# BLUEPILL_full_schematic_for_BRD.net
KiCad netlist of a schematic drawn in EAGLE
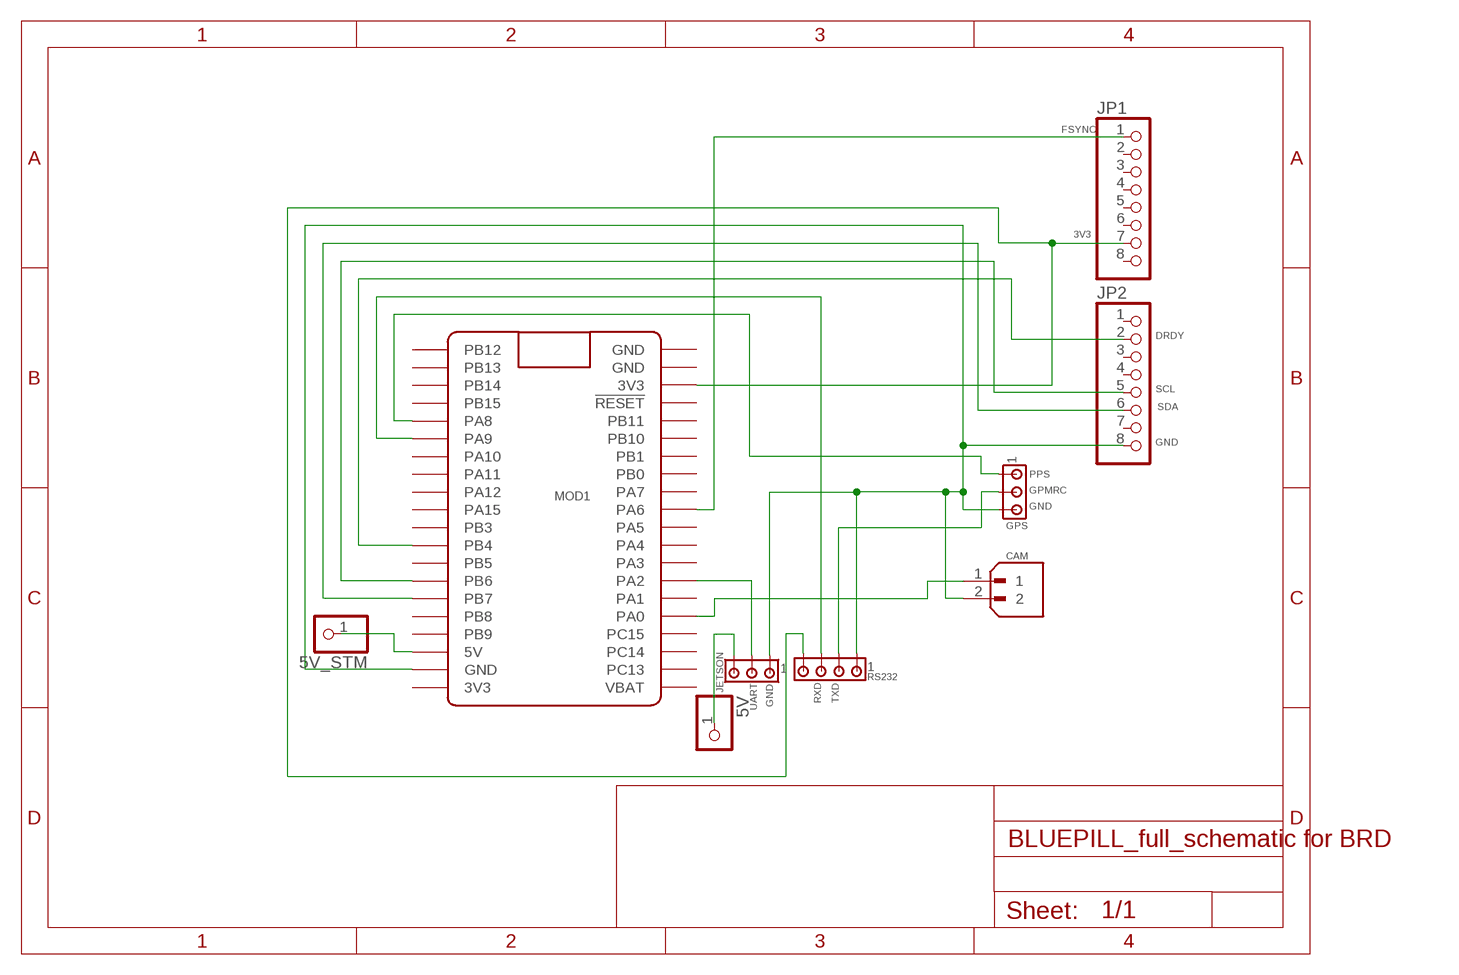
[diagram p0: schematic, sheet 1]

(export (version "E")
  (design (tool "Eeschema 10.0.6"))
  (components
    (comp (ref "5V")
      (value "PINHD-1X1")
      (footprint "eagle-import:1X01")
      (libsource (lib "eagle-import") (part "PINHD-1X1"))
    )
    (comp (ref "5V_STM")
      (value "PINHD-1X1")
      (footprint "eagle-import:1X01")
      (libsource (lib "eagle-import") (part "PINHD-1X1"))
    )
    (comp (ref "CAM")
      (value "B2B-XH-A")
      (footprint "eagle-import:JST_B2B-XH-A")
      (fields (field (name "MF") "JST Sales"))
      (libsource (lib "eagle-import") (part "B2B-XH-A"))
    )
    (comp (ref "GPS")
      (value "MTA03-100")
      (footprint "eagle-import:10X03MTA")
      (libsource (lib "eagle-import") (part "MTA03-100"))
    )
    (comp (ref "JETSON")
      (value "MTA03-100")
      (footprint "eagle-import:10X03MTA")
      (libsource (lib "eagle-import") (part "MTA03-100"))
    )
    (comp (ref "JP1")
      (value "PINHD-1X8")
      (footprint "eagle-import:1X08")
      (libsource (lib "eagle-import") (part "PINHD-1X8"))
    )
    (comp (ref "JP2")
      (value "PINHD-1X8")
      (footprint "eagle-import:1X08")
      (libsource (lib "eagle-import") (part "PINHD-1X8"))
    )
    (comp (ref "MOD1")
      (value "BLUE_PILL")
      (footprint "eagle-import:BLUE_PILL")
      (libsource (lib "eagle-import") (part "BLUE_PILL"))
    )
    (comp (ref "RS232")
      (value "MTA04-100")
      (footprint "eagle-import:10X04MTA")
      (libsource (lib "eagle-import") (part "MTA04-100"))
    )
  )
  (nets
    (net (code "1") (name "/3V3") (class "Default")
      (node (ref "JP1") (pin "7") (pinfunction "7_7") (pintype "passive"))
      (node (ref "MOD1") (pin "P$23") (pinfunction "3V3_P$23") (pintype "bidirectional"))
      (node (ref "RS232") (pin "4") (pinfunction "4_4") (pintype "passive"))
    )
    (net (code "2") (name "/DRDY") (class "Default")
      (node (ref "JP2") (pin "2") (pinfunction "2_2") (pintype "passive"))
      (node (ref "MOD1") (pin "P$12") (pinfunction "PB4_P$12") (pintype "bidirectional"))
    )
    (net (code "3") (name "/FSYNC") (class "Default")
      (node (ref "JP1") (pin "1") (pinfunction "1_1") (pintype "passive"))
      (node (ref "MOD1") (pin "P$30") (pinfunction "PA6_P$30") (pintype "bidirectional"))
    )
    (net (code "4") (name "/GND") (class "Default")
      (node (ref "CAM") (pin "2") (pinfunction "2_2") (pintype "passive"))
      (node (ref "GPS") (pin "3") (pinfunction "3_3") (pintype "passive"))
      (node (ref "JETSON") (pin "1") (pinfunction "1_1") (pintype "passive"))
      (node (ref "JP2") (pin "8") (pinfunction "8_8") (pintype "passive"))
      (node (ref "MOD1") (pin "P$19") (pinfunction "GND_P$19") (pintype "passive"))
      (node (ref "RS232") (pin "1") (pinfunction "1_1") (pintype "passive"))
    )
    (net (code "5") (name "/PPS") (class "Default")
      (node (ref "GPS") (pin "1") (pinfunction "1_1") (pintype "passive"))
      (node (ref "MOD1") (pin "P$5") (pinfunction "PA8_P$5") (pintype "bidirectional"))
    )
    (net (code "6") (name "/RXD") (class "Default")
      (node (ref "MOD1") (pin "P$6") (pinfunction "PA9_P$6") (pintype "bidirectional"))
      (node (ref "RS232") (pin "3") (pinfunction "3_3") (pintype "passive"))
    )
    (net (code "7") (name "/SCL") (class "Default")
      (node (ref "JP2") (pin "5") (pinfunction "5_5") (pintype "passive"))
      (node (ref "MOD1") (pin "P$14") (pinfunction "PB6_P$14") (pintype "bidirectional"))
    )
    (net (code "8") (name "/SDA") (class "Default")
      (node (ref "JP2") (pin "6") (pinfunction "6_6") (pintype "passive"))
      (node (ref "MOD1") (pin "P$15") (pinfunction "PB7_P$15") (pintype "bidirectional"))
    )
    (net (code "9") (name "/TXD") (class "Default")
      (node (ref "GPS") (pin "2") (pinfunction "2_2") (pintype "passive"))
      (node (ref "RS232") (pin "2") (pinfunction "2_2") (pintype "passive"))
    )
    (net (code "10") (name "Net-(5V-Pad1)") (class "Default")
      (node (ref "5V") (pin "1") (pinfunction "1_1") (pintype "passive"))
      (node (ref "JETSON") (pin "3") (pinfunction "3_3") (pintype "passive"))
    )
    (net (code "11") (name "Net-(MOD1-5V)") (class "Default")
      (node (ref "5V_STM") (pin "1") (pinfunction "1_1") (pintype "passive"))
      (node (ref "MOD1") (pin "P$18") (pinfunction "5V_P$18") (pintype "bidirectional"))
    )
    (net (code "12") (name "Net-(MOD1-PA0)") (class "Default")
      (node (ref "CAM") (pin "1") (pinfunction "1_1") (pintype "passive"))
      (node (ref "MOD1") (pin "P$36") (pinfunction "PA0_P$36") (pintype "bidirectional"))
    )
    (net (code "13") (name "Net-(MOD1-PA2)") (class "Default")
      (node (ref "JETSON") (pin "2") (pinfunction "2_2") (pintype "passive"))
      (node (ref "MOD1") (pin "P$34") (pinfunction "PA2_P$34") (pintype "bidirectional"))
    )
    (net (code "14") (name "unconnected-(JP1-Pad2)") (class "Default")
      (node (ref "JP1") (pin "2") (pinfunction "2_2") (pintype "passive"))
    )
    (net (code "15") (name "unconnected-(JP1-Pad3)") (class "Default")
      (node (ref "JP1") (pin "3") (pinfunction "3_3") (pintype "passive"))
    )
    (net (code "16") (name "unconnected-(JP1-Pad4)") (class "Default")
      (node (ref "JP1") (pin "4") (pinfunction "4_4") (pintype "passive"))
    )
    (net (code "17") (name "unconnected-(JP1-Pad5)") (class "Default")
      (node (ref "JP1") (pin "5") (pinfunction "5_5") (pintype "passive"))
    )
    (net (code "18") (name "unconnected-(JP1-Pad6)") (class "Default")
      (node (ref "JP1") (pin "6") (pinfunction "6_6") (pintype "passive"))
    )
    (net (code "19") (name "unconnected-(JP1-Pad8)") (class "Default")
      (node (ref "JP1") (pin "8") (pinfunction "8_8") (pintype "passive"))
    )
    (net (code "20") (name "unconnected-(JP2-Pad1)") (class "Default")
      (node (ref "JP2") (pin "1") (pinfunction "1_1") (pintype "passive"))
    )
    (net (code "21") (name "unconnected-(JP2-Pad3)") (class "Default")
      (node (ref "JP2") (pin "3") (pinfunction "3_3") (pintype "passive"))
    )
    (net (code "22") (name "unconnected-(JP2-Pad4)") (class "Default")
      (node (ref "JP2") (pin "4") (pinfunction "4_4") (pintype "passive"))
    )
    (net (code "23") (name "unconnected-(JP2-Pad7)") (class "Default")
      (node (ref "JP2") (pin "7") (pinfunction "7_7") (pintype "passive"))
    )
    (net (code "24") (name "unconnected-(MOD1-3V3-PadP$20)") (class "Default")
      (node (ref "MOD1") (pin "P$20") (pinfunction "3V3_P$20") (pintype "bidirectional"))
    )
    (net (code "25") (name "unconnected-(MOD1-GND-PadP$21)") (class "Default")
      (node (ref "MOD1") (pin "P$21") (pinfunction "GND_P$21") (pintype "passive"))
    )
    (net (code "26") (name "unconnected-(MOD1-GND-PadP$22)") (class "Default")
      (node (ref "MOD1") (pin "P$22") (pinfunction "GND_P$22") (pintype "passive"))
    )
    (net (code "27") (name "unconnected-(MOD1-PA1-PadP$35)") (class "Default")
      (node (ref "MOD1") (pin "P$35") (pinfunction "PA1_P$35") (pintype "bidirectional"))
    )
    (net (code "28") (name "unconnected-(MOD1-PA3-PadP$33)") (class "Default")
      (node (ref "MOD1") (pin "P$33") (pinfunction "PA3_P$33") (pintype "bidirectional"))
    )
    (net (code "29") (name "unconnected-(MOD1-PA4-PadP$32)") (class "Default")
      (node (ref "MOD1") (pin "P$32") (pinfunction "PA4_P$32") (pintype "bidirectional"))
    )
    (net (code "30") (name "unconnected-(MOD1-PA5-PadP$31)") (class "Default")
      (node (ref "MOD1") (pin "P$31") (pinfunction "PA5_P$31") (pintype "bidirectional"))
    )
    (net (code "31") (name "unconnected-(MOD1-PA7-PadP$29)") (class "Default")
      (node (ref "MOD1") (pin "P$29") (pinfunction "PA7_P$29") (pintype "bidirectional"))
    )
    (net (code "32") (name "unconnected-(MOD1-PA10-PadP$7)") (class "Default")
      (node (ref "MOD1") (pin "P$7") (pinfunction "PA10_P$7") (pintype "bidirectional"))
    )
    (net (code "33") (name "unconnected-(MOD1-PA11-PadP$8)") (class "Default")
      (node (ref "MOD1") (pin "P$8") (pinfunction "PA11_P$8") (pintype "bidirectional"))
    )
    (net (code "34") (name "unconnected-(MOD1-PA12-PadP$9)") (class "Default")
      (node (ref "MOD1") (pin "P$9") (pinfunction "PA12_P$9") (pintype "bidirectional"))
    )
    (net (code "35") (name "unconnected-(MOD1-PA15-PadP$10)") (class "Default")
      (node (ref "MOD1") (pin "P$10") (pinfunction "PA15_P$10") (pintype "bidirectional"))
    )
    (net (code "36") (name "unconnected-(MOD1-PB0-PadP$28)") (class "Default")
      (node (ref "MOD1") (pin "P$28") (pinfunction "PB0_P$28") (pintype "bidirectional"))
    )
    (net (code "37") (name "unconnected-(MOD1-PB1-PadP$27)") (class "Default")
      (node (ref "MOD1") (pin "P$27") (pinfunction "PB1_P$27") (pintype "bidirectional"))
    )
    (net (code "38") (name "unconnected-(MOD1-PB3-PadP$11)") (class "Default")
      (node (ref "MOD1") (pin "P$11") (pinfunction "PB3_P$11") (pintype "bidirectional"))
    )
    (net (code "39") (name "unconnected-(MOD1-PB5-PadP$13)") (class "Default")
      (node (ref "MOD1") (pin "P$13") (pinfunction "PB5_P$13") (pintype "bidirectional"))
    )
    (net (code "40") (name "unconnected-(MOD1-PB8-PadP$16)") (class "Default")
      (node (ref "MOD1") (pin "P$16") (pinfunction "PB8_P$16") (pintype "bidirectional"))
    )
    (net (code "41") (name "unconnected-(MOD1-PB9-PadP$17)") (class "Default")
      (node (ref "MOD1") (pin "P$17") (pinfunction "PB9_P$17") (pintype "bidirectional"))
    )
    (net (code "42") (name "unconnected-(MOD1-PB10-PadP$26)") (class "Default")
      (node (ref "MOD1") (pin "P$26") (pinfunction "PB10_P$26") (pintype "bidirectional"))
    )
    (net (code "43") (name "unconnected-(MOD1-PB11-PadP$25)") (class "Default")
      (node (ref "MOD1") (pin "P$25") (pinfunction "PB11_P$25") (pintype "bidirectional"))
    )
    (net (code "44") (name "unconnected-(MOD1-PB12-PadP$1)") (class "Default")
      (node (ref "MOD1") (pin "P$1") (pinfunction "PB12_P$1") (pintype "bidirectional"))
    )
    (net (code "45") (name "unconnected-(MOD1-PB13-PadP$2)") (class "Default")
      (node (ref "MOD1") (pin "P$2") (pinfunction "PB13_P$2") (pintype "bidirectional"))
    )
    (net (code "46") (name "unconnected-(MOD1-PB14-PadP$3)") (class "Default")
      (node (ref "MOD1") (pin "P$3") (pinfunction "PB14_P$3") (pintype "bidirectional"))
    )
    (net (code "47") (name "unconnected-(MOD1-PB15-PadP$4)") (class "Default")
      (node (ref "MOD1") (pin "P$4") (pinfunction "PB15_P$4") (pintype "bidirectional"))
    )
    (net (code "48") (name "unconnected-(MOD1-PC13-PadP$39)") (class "Default")
      (node (ref "MOD1") (pin "P$39") (pinfunction "PC13_P$39") (pintype "bidirectional"))
    )
    (net (code "49") (name "unconnected-(MOD1-PC14-PadP$38)") (class "Default")
      (node (ref "MOD1") (pin "P$38") (pinfunction "PC14_P$38") (pintype "bidirectional"))
    )
    (net (code "50") (name "unconnected-(MOD1-PC15-PadP$37)") (class "Default")
      (node (ref "MOD1") (pin "P$37") (pinfunction "PC15_P$37") (pintype "bidirectional"))
    )
    (net (code "51") (name "unconnected-(MOD1-VBAT-PadP$40)") (class "Default")
      (node (ref "MOD1") (pin "P$40") (pinfunction "VBAT_P$40") (pintype "bidirectional"))
    )
    (net (code "52") (name "unconnected-(MOD1-~{RESET}-PadP$24)") (class "Default")
      (node (ref "MOD1") (pin "P$24") (pinfunction "~{RESET}_P$24") (pintype "bidirectional"))
    )
  )
)
